# eeprom_burner.net
KiCad netlist of a schematic drawn in EAGLE
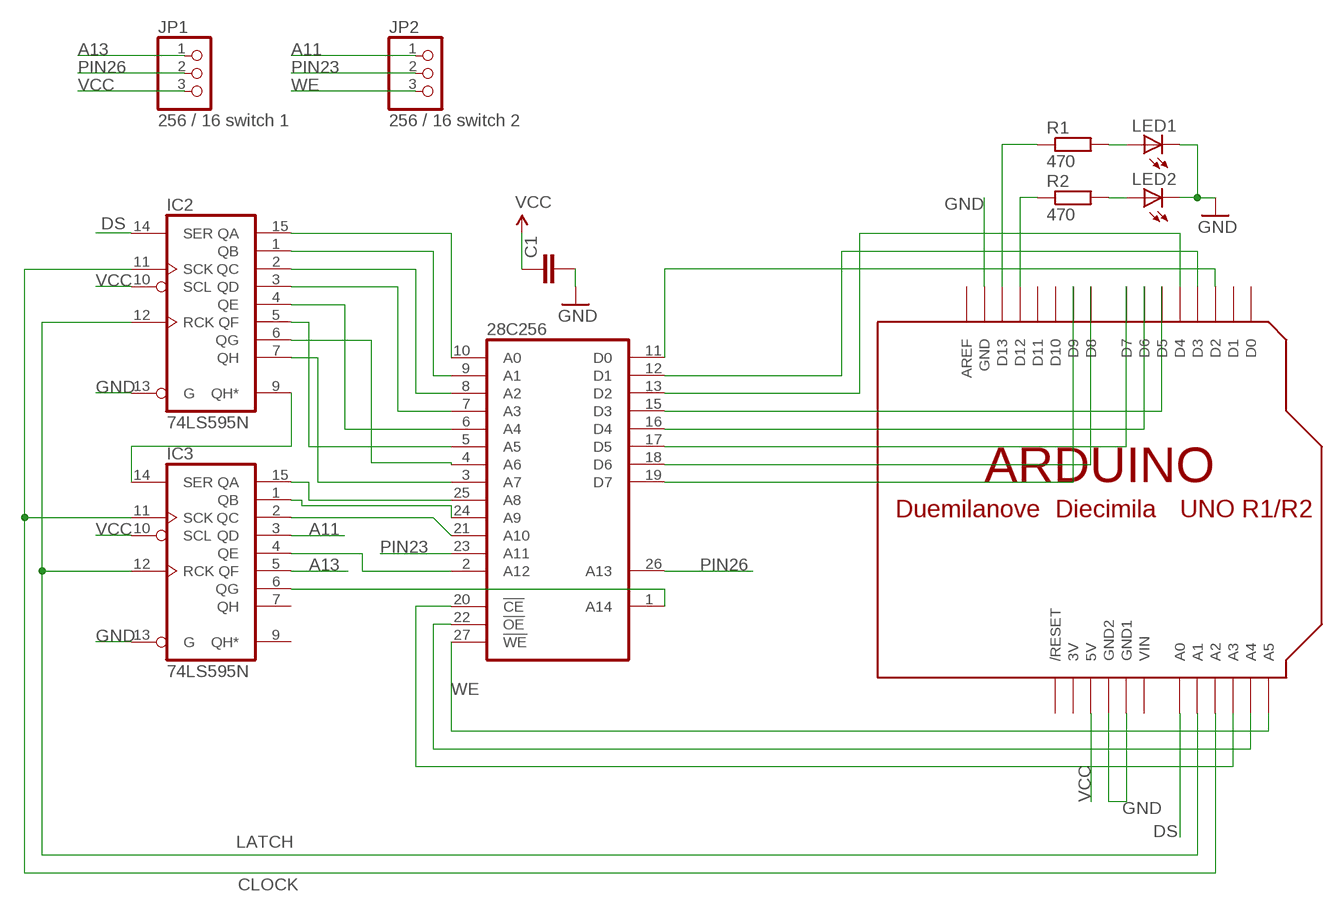
[diagram p0: schematic, sheet 1]

(export (version "E")
  (design (tool "Eeschema 10.0.6"))
  (components
    (comp (ref "28C256")
      (value "2864")
      (footprint "eagle-import:DIL28")
      (libsource (lib "eagle-import") (part "2864"))
    )
    (comp (ref "C1")
      (value "CAPPTH")
      (footprint "eagle-import:CAP-PTH-SMALL")
      (libsource (lib "eagle-import") (part "CAPPTH"))
    )
    (comp (ref "IC2")
      (value "74LS595N")
      (footprint "eagle-import:DIL16")
      (libsource (lib "eagle-import") (part "74595NLS"))
    )
    (comp (ref "IC3")
      (value "74LS595N")
      (footprint "eagle-import:DIL16")
      (libsource (lib "eagle-import") (part "74595NLS"))
    )
    (comp (ref "JP1")
      (value "256 / 16 switch 1")
      (footprint "eagle-import:1X03")
      (libsource (lib "eagle-import") (part "PINHD-1X3"))
    )
    (comp (ref "JP2")
      (value "256 / 16 switch 2")
      (footprint "eagle-import:1X03")
      (libsource (lib "eagle-import") (part "PINHD-1X3"))
    )
    (comp (ref "LED1")
      (value "LED3MM")
      (footprint "eagle-import:LED3MM")
      (libsource (lib "eagle-import") (part "LED3MM"))
    )
    (comp (ref "LED2")
      (value "LED3MM")
      (footprint "eagle-import:LED3MM")
      (libsource (lib "eagle-import") (part "LED3MM"))
    )
    (comp (ref "R1")
      (value "470")
      (footprint "eagle-import:0204_7")
      (libsource (lib "eagle-import") (part "R-EU_0204/7"))
    )
    (comp (ref "R2")
      (value "470")
      (footprint "eagle-import:0204_7")
      (libsource (lib "eagle-import") (part "R-EU_0204/7"))
    )
    (comp (ref "U$1")
      (value "ARDUINO-NODIM")
      (footprint "eagle-import:ARDUINO-NODIM")
      (libsource (lib "eagle-import") (part "ARDUINO-NODIM"))
    )
  )
  (nets
    (net (code "1") (name "/3V") (class "Default")
      (node (ref "U$1") (pin "3V") (pinfunction "3V_3V") (pintype "power_in"))
    )
    (net (code "2") (name "/A11") (class "Default")
      (node (ref "IC3") (pin "3") (pinfunction "QD_3") (pintype "tri_state"))
      (node (ref "JP2") (pin "1") (pinfunction "1_1") (pintype "passive"))
    )
    (net (code "3") (name "/A13") (class "Default")
      (node (ref "IC3") (pin "5") (pinfunction "QF_5") (pintype "tri_state"))
      (node (ref "JP1") (pin "1") (pinfunction "1_1") (pintype "passive"))
    )
    (net (code "4") (name "/CLOCK") (class "Default")
      (node (ref "IC2") (pin "11") (pinfunction "SCK_11") (pintype "input"))
      (node (ref "IC3") (pin "11") (pinfunction "SCK_11") (pintype "input"))
      (node (ref "U$1") (pin "A2") (pinfunction "A2_A2") (pintype "bidirectional"))
    )
    (net (code "5") (name "/DS") (class "Default")
      (node (ref "IC2") (pin "14") (pinfunction "SER_14") (pintype "input"))
      (node (ref "U$1") (pin "A0") (pinfunction "A0_A0") (pintype "bidirectional"))
    )
    (net (code "6") (name "/LATCH") (class "Default")
      (node (ref "IC2") (pin "12") (pinfunction "RCK_12") (pintype "input"))
      (node (ref "IC3") (pin "12") (pinfunction "RCK_12") (pintype "input"))
      (node (ref "U$1") (pin "A1") (pinfunction "A1_A1") (pintype "bidirectional"))
    )
    (net (code "7") (name "/PIN23") (class "Default")
      (node (ref "28C256") (pin "23") (pinfunction "A11_23") (pintype "input"))
      (node (ref "JP2") (pin "2") (pinfunction "2_2") (pintype "passive"))
    )
    (net (code "8") (name "/PIN26") (class "Default")
      (node (ref "28C256") (pin "26") (pinfunction "A13_26") (pintype "input"))
      (node (ref "JP1") (pin "2") (pinfunction "2_2") (pintype "passive"))
    )
    (net (code "9") (name "/VIN") (class "Default")
      (node (ref "U$1") (pin "VIN") (pinfunction "VIN_VIN") (pintype "power_in"))
    )
    (net (code "10") (name "/WE") (class "Default")
      (node (ref "28C256") (pin "27") (pinfunction "~{WE}_27") (pintype "input"))
      (node (ref "JP2") (pin "3") (pinfunction "3_3") (pintype "passive"))
      (node (ref "U$1") (pin "A5") (pinfunction "A5_A5") (pintype "bidirectional"))
    )
    (net (code "11") (name "GND") (class "Default")
      (node (ref "C1") (pin "2") (pinfunction "2_2") (pintype "passive"))
      (node (ref "IC2") (pin "13") (pinfunction "G_13") (pintype "input"))
      (node (ref "IC3") (pin "13") (pinfunction "G_13") (pintype "input"))
      (node (ref "LED1") (pin "K") (pinfunction "C_K") (pintype "passive"))
      (node (ref "LED2") (pin "K") (pinfunction "C_K") (pintype "passive"))
      (node (ref "U$1") (pin "GND") (pinfunction "GND_GND") (pintype "power_in"))
      (node (ref "U$1") (pin "GND1") (pinfunction "GND1_GND1") (pintype "power_in"))
      (node (ref "U$1") (pin "GND2") (pinfunction "GND2_GND2") (pintype "power_in"))
    )
    (net (code "12") (name "Net-(28C256A-A0)") (class "Default")
      (node (ref "28C256") (pin "10") (pinfunction "A0_10") (pintype "input"))
      (node (ref "IC2") (pin "15") (pinfunction "QA_15") (pintype "tri_state"))
    )
    (net (code "13") (name "Net-(28C256A-A1)") (class "Default")
      (node (ref "28C256") (pin "9") (pinfunction "A1_9") (pintype "input"))
      (node (ref "IC2") (pin "1") (pinfunction "QB_1") (pintype "tri_state"))
    )
    (net (code "14") (name "Net-(28C256A-A2)") (class "Default")
      (node (ref "28C256") (pin "8") (pinfunction "A2_8") (pintype "input"))
      (node (ref "IC2") (pin "2") (pinfunction "QC_2") (pintype "tri_state"))
    )
    (net (code "15") (name "Net-(28C256A-A3)") (class "Default")
      (node (ref "28C256") (pin "7") (pinfunction "A3_7") (pintype "input"))
      (node (ref "IC2") (pin "3") (pinfunction "QD_3") (pintype "tri_state"))
    )
    (net (code "16") (name "Net-(28C256A-A4)") (class "Default")
      (node (ref "28C256") (pin "6") (pinfunction "A4_6") (pintype "input"))
      (node (ref "IC2") (pin "4") (pinfunction "QE_4") (pintype "tri_state"))
    )
    (net (code "17") (name "Net-(28C256A-A5)") (class "Default")
      (node (ref "28C256") (pin "5") (pinfunction "A5_5") (pintype "input"))
      (node (ref "IC2") (pin "5") (pinfunction "QF_5") (pintype "tri_state"))
    )
    (net (code "18") (name "Net-(28C256A-A6)") (class "Default")
      (node (ref "28C256") (pin "4") (pinfunction "A6_4") (pintype "input"))
      (node (ref "IC2") (pin "6") (pinfunction "QG_6") (pintype "tri_state"))
    )
    (net (code "19") (name "Net-(28C256A-A7)") (class "Default")
      (node (ref "28C256") (pin "3") (pinfunction "A7_3") (pintype "input"))
      (node (ref "IC2") (pin "7") (pinfunction "QH_7") (pintype "tri_state"))
    )
    (net (code "20") (name "Net-(28C256A-A8)") (class "Default")
      (node (ref "28C256") (pin "25") (pinfunction "A8_25") (pintype "input"))
      (node (ref "IC3") (pin "15") (pinfunction "QA_15") (pintype "tri_state"))
    )
    (net (code "21") (name "Net-(28C256A-A9)") (class "Default")
      (node (ref "28C256") (pin "24") (pinfunction "A9_24") (pintype "input"))
      (node (ref "IC3") (pin "1") (pinfunction "QB_1") (pintype "tri_state"))
    )
    (net (code "22") (name "Net-(28C256A-A10)") (class "Default")
      (node (ref "28C256") (pin "21") (pinfunction "A10_21") (pintype "input"))
      (node (ref "IC3") (pin "2") (pinfunction "QC_2") (pintype "tri_state"))
    )
    (net (code "23") (name "Net-(28C256A-A12)") (class "Default")
      (node (ref "28C256") (pin "2") (pinfunction "A12_2") (pintype "input"))
      (node (ref "IC3") (pin "4") (pinfunction "QE_4") (pintype "tri_state"))
    )
    (net (code "24") (name "Net-(28C256A-A14)") (class "Default")
      (node (ref "28C256") (pin "1") (pinfunction "A14_1") (pintype "input"))
      (node (ref "IC3") (pin "6") (pinfunction "QG_6") (pintype "tri_state"))
    )
    (net (code "25") (name "Net-(28C256A-D0)") (class "Default")
      (node (ref "28C256") (pin "11") (pinfunction "D0_11") (pintype "bidirectional"))
      (node (ref "U$1") (pin "D2") (pinfunction "D2_D2") (pintype "bidirectional"))
    )
    (net (code "26") (name "Net-(28C256A-D1)") (class "Default")
      (node (ref "28C256") (pin "12") (pinfunction "D1_12") (pintype "bidirectional"))
      (node (ref "U$1") (pin "D3") (pinfunction "D3_D3") (pintype "bidirectional"))
    )
    (net (code "27") (name "Net-(28C256A-D2)") (class "Default")
      (node (ref "28C256") (pin "13") (pinfunction "D2_13") (pintype "bidirectional"))
      (node (ref "U$1") (pin "D4") (pinfunction "D4_D4") (pintype "bidirectional"))
    )
    (net (code "28") (name "Net-(28C256A-D3)") (class "Default")
      (node (ref "28C256") (pin "15") (pinfunction "D3_15") (pintype "bidirectional"))
      (node (ref "U$1") (pin "D5") (pinfunction "D5_D5") (pintype "bidirectional"))
    )
    (net (code "29") (name "Net-(28C256A-D4)") (class "Default")
      (node (ref "28C256") (pin "16") (pinfunction "D4_16") (pintype "bidirectional"))
      (node (ref "U$1") (pin "D6") (pinfunction "D6_D6") (pintype "bidirectional"))
    )
    (net (code "30") (name "Net-(28C256A-D5)") (class "Default")
      (node (ref "28C256") (pin "17") (pinfunction "D5_17") (pintype "bidirectional"))
      (node (ref "U$1") (pin "D7") (pinfunction "D7_D7") (pintype "bidirectional"))
    )
    (net (code "31") (name "Net-(28C256A-D6)") (class "Default")
      (node (ref "28C256") (pin "18") (pinfunction "D6_18") (pintype "bidirectional"))
      (node (ref "U$1") (pin "D8") (pinfunction "D8_D8") (pintype "bidirectional"))
    )
    (net (code "32") (name "Net-(28C256A-D7)") (class "Default")
      (node (ref "28C256") (pin "19") (pinfunction "D7_19") (pintype "bidirectional"))
      (node (ref "U$1") (pin "D9") (pinfunction "D9_D9") (pintype "bidirectional"))
    )
    (net (code "33") (name "Net-(28C256A-~{CE})") (class "Default")
      (node (ref "28C256") (pin "20") (pinfunction "~{CE}_20") (pintype "input"))
      (node (ref "U$1") (pin "A3") (pinfunction "A3_A3") (pintype "bidirectional"))
    )
    (net (code "34") (name "Net-(28C256A-~{OE})") (class "Default")
      (node (ref "28C256") (pin "22") (pinfunction "~{OE}_22") (pintype "input"))
      (node (ref "U$1") (pin "A4") (pinfunction "A4_A4") (pintype "bidirectional"))
    )
    (net (code "35") (name "Net-(IC2A-QH*)") (class "Default")
      (node (ref "IC2") (pin "9") (pinfunction "QH*_9") (pintype "tri_state"))
      (node (ref "IC3") (pin "14") (pinfunction "SER_14") (pintype "input"))
    )
    (net (code "36") (name "Net-(LED1-PadA)") (class "Default")
      (node (ref "LED1") (pin "A") (pinfunction "A_A") (pintype "passive"))
      (node (ref "R1") (pin "2") (pinfunction "2_2") (pintype "passive"))
    )
    (net (code "37") (name "Net-(LED2-PadA)") (class "Default")
      (node (ref "LED2") (pin "A") (pinfunction "A_A") (pintype "passive"))
      (node (ref "R2") (pin "2") (pinfunction "2_2") (pintype "passive"))
    )
    (net (code "38") (name "Net-(R1-Pad1)") (class "Default")
      (node (ref "R1") (pin "1") (pinfunction "1_1") (pintype "passive"))
      (node (ref "U$1") (pin "D13") (pinfunction "D13_D13") (pintype "bidirectional"))
    )
    (net (code "39") (name "Net-(R2-Pad1)") (class "Default")
      (node (ref "R2") (pin "1") (pinfunction "1_1") (pintype "passive"))
      (node (ref "U$1") (pin "D12") (pinfunction "D12_D12") (pintype "bidirectional"))
    )
    (net (code "40") (name "VCC") (class "Default")
      (node (ref "C1") (pin "1") (pinfunction "1_1") (pintype "passive"))
      (node (ref "IC2") (pin "10") (pinfunction "SCL_10") (pintype "input"))
      (node (ref "IC3") (pin "10") (pinfunction "SCL_10") (pintype "input"))
      (node (ref "JP1") (pin "3") (pinfunction "3_3") (pintype "passive"))
      (node (ref "U$1") (pin "5V") (pinfunction "5V_5V") (pintype "power_in"))
    )
    (net (code "41") (name "unconnected-(IC3A-QH*-Pad9)") (class "Default")
      (node (ref "IC3") (pin "9") (pinfunction "QH*_9") (pintype "tri_state"))
    )
    (net (code "42") (name "unconnected-(IC3A-QH-Pad7)") (class "Default")
      (node (ref "IC3") (pin "7") (pinfunction "QH_7") (pintype "tri_state"))
    )
    (net (code "43") (name "unconnected-(U$1-PadAREF)") (class "Default")
      (node (ref "U$1") (pin "AREF") (pinfunction "AREF_AREF") (pintype "bidirectional"))
    )
    (net (code "44") (name "unconnected-(U$1-PadD0)") (class "Default")
      (node (ref "U$1") (pin "D0") (pinfunction "D0_D0") (pintype "bidirectional"))
    )
    (net (code "45") (name "unconnected-(U$1-PadD1)") (class "Default")
      (node (ref "U$1") (pin "D1") (pinfunction "D1_D1") (pintype "bidirectional"))
    )
    (net (code "46") (name "unconnected-(U$1-PadD10)") (class "Default")
      (node (ref "U$1") (pin "D10") (pinfunction "D10_D10") (pintype "bidirectional"))
    )
    (net (code "47") (name "unconnected-(U$1-PadD11)") (class "Default")
      (node (ref "U$1") (pin "D11") (pinfunction "D11_D11") (pintype "bidirectional"))
    )
    (net (code "48") (name "unconnected-(U$1-{slash}RESET-PadRESET)") (class "Default")
      (node (ref "U$1") (pin "RESET") (pinfunction "/RESET_RESET") (pintype "bidirectional"))
    )
  )
)
